# Power.net
KiCad netlist of a schematic drawn in Altium Designer
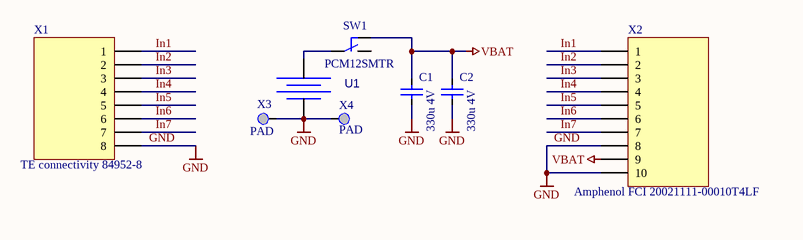
[diagram p0: Power.SchDoc]

(export (version "E")
  (design (tool "Eeschema 10.0.6"))
  (components
    (comp (ref "C1")
      (value "330u 4V")
      (footprint "CAPC3225L")
      (description "Capacitor")
      (fields (field (name "PARTNUMBER") "490-13976-1-ND #Digikey"))
      (libsource (lib "ECOG") (part "Capacitor"))
    )
    (comp (ref "C2")
      (value "330u 4V")
      (footprint "CAPC3225L")
      (description "Capacitor")
      (fields (field (name "PARTNUMBER") "490-13976-1-ND #Digikey"))
      (libsource (lib "ECOG") (part "Capacitor"))
    )
    (comp (ref "SW1")
      (value "PCM12SMTR")
      (footprint "PCM12SMTR")
      (description "Miniature Surface Mount Switches")
      (fields (field (name "PARTNUMBER") "401-2016-1-ND #Digikey"))
      (libsource (lib "ECOG") (part "SPDT"))
    )
    (comp (ref "U1")
      (value "Keystone 3000")
      (footprint "BK-3000")
      (description "Battery")
      (fields (field (name "PARTNUMBER") "36-3000CT-ND #Digikey"))
      (libsource (lib "ECOG") (part "Battery"))
    )
    (comp (ref "X1")
      (value "TE connectivity 84952-8")
      (footprint "ZIF connector 84952-8")
      (description "Header")
      (fields (field (name "PARTNUMBER") "A100249CT-ND #Digikey"))
      (libsource (lib "ECOG") (part "DB-8F"))
    )
    (comp (ref "X2")
      (value "Amphenol FCI 20021111-00010T4LF")
      (footprint "HDR-1.27mm-2X5")
      (description "Header")
      (fields (field (name "PARTNUMBER") "609-3712-ND #Digikey"))
      (libsource (lib "ECOG") (part "DB-10F"))
    )
    (comp (ref "X3") (value "PAD") (footprint "PAD3mm") (libsource (lib "ECOG") (part "PAD")))
    (comp (ref "X4") (value "PAD") (footprint "PAD3mm") (libsource (lib "ECOG") (part "PAD")))
  )
  (nets
    (net (code "1") (name "/In1") (class "Default")
      (node (ref "X1") (pin "1") (pinfunction "1_1") (pintype "passive"))
      (node (ref "X2") (pin "1") (pinfunction "1_1") (pintype "passive"))
    )
    (net (code "2") (name "/In2") (class "Default")
      (node (ref "X1") (pin "2") (pinfunction "2_2") (pintype "passive"))
      (node (ref "X2") (pin "2") (pinfunction "2_2") (pintype "passive"))
    )
    (net (code "3") (name "/In3") (class "Default")
      (node (ref "X1") (pin "3") (pinfunction "3_3") (pintype "passive"))
      (node (ref "X2") (pin "3") (pinfunction "3_3") (pintype "passive"))
    )
    (net (code "4") (name "/In4") (class "Default")
      (node (ref "X1") (pin "4") (pinfunction "4_4") (pintype "passive"))
      (node (ref "X2") (pin "4") (pinfunction "4_4") (pintype "passive"))
    )
    (net (code "5") (name "/In5") (class "Default")
      (node (ref "X1") (pin "5") (pinfunction "5_5") (pintype "passive"))
      (node (ref "X2") (pin "5") (pinfunction "5_5") (pintype "passive"))
    )
    (net (code "6") (name "/In6") (class "Default")
      (node (ref "X1") (pin "6") (pinfunction "6_6") (pintype "passive"))
      (node (ref "X2") (pin "6") (pinfunction "6_6") (pintype "passive"))
    )
    (net (code "7") (name "/In7") (class "Default")
      (node (ref "X1") (pin "7") (pinfunction "7_7") (pintype "passive"))
      (node (ref "X2") (pin "7") (pinfunction "7_7") (pintype "passive"))
    )
    (net (code "8") (name "GND") (class "Default")
      (node (ref "C1") (pin "2") (pinfunction "2_2") (pintype "passive"))
      (node (ref "C2") (pin "2") (pinfunction "2_2") (pintype "passive"))
      (node (ref "U1") (pin "2") (pinfunction "-_2") (pintype "passive"))
      (node (ref "X1") (pin "8") (pinfunction "8_8") (pintype "passive"))
      (node (ref "X2") (pin "10") (pinfunction "10_10") (pintype "passive"))
      (node (ref "X2") (pin "8") (pinfunction "8_8") (pintype "passive"))
      (node (ref "X3") (pin "1") (pintype "passive"))
      (node (ref "X4") (pin "1") (pintype "passive"))
    )
    (net (code "9") (name "Net-(U1-+)") (class "Default")
      (node (ref "SW1") (pin "2") (pinfunction "2_2") (pintype "passive"))
      (node (ref "U1") (pin "1") (pinfunction "+_1") (pintype "passive"))
    )
    (net (code "10") (name "VBAT") (class "Default")
      (node (ref "C1") (pin "1") (pinfunction "1_1") (pintype "passive"))
      (node (ref "C2") (pin "1") (pinfunction "1_1") (pintype "passive"))
      (node (ref "SW1") (pin "3") (pinfunction "3_3") (pintype "passive"))
      (node (ref "X2") (pin "9") (pinfunction "9_9") (pintype "passive"))
    )
    (net (code "11") (name "unconnected-(SW1-Pad1)") (class "Default")
      (node (ref "SW1") (pin "1") (pinfunction "1_1") (pintype "passive"))
    )
  )
)
